# papilio_cam_board.net
KiCad netlist of a schematic drawn in EAGLE
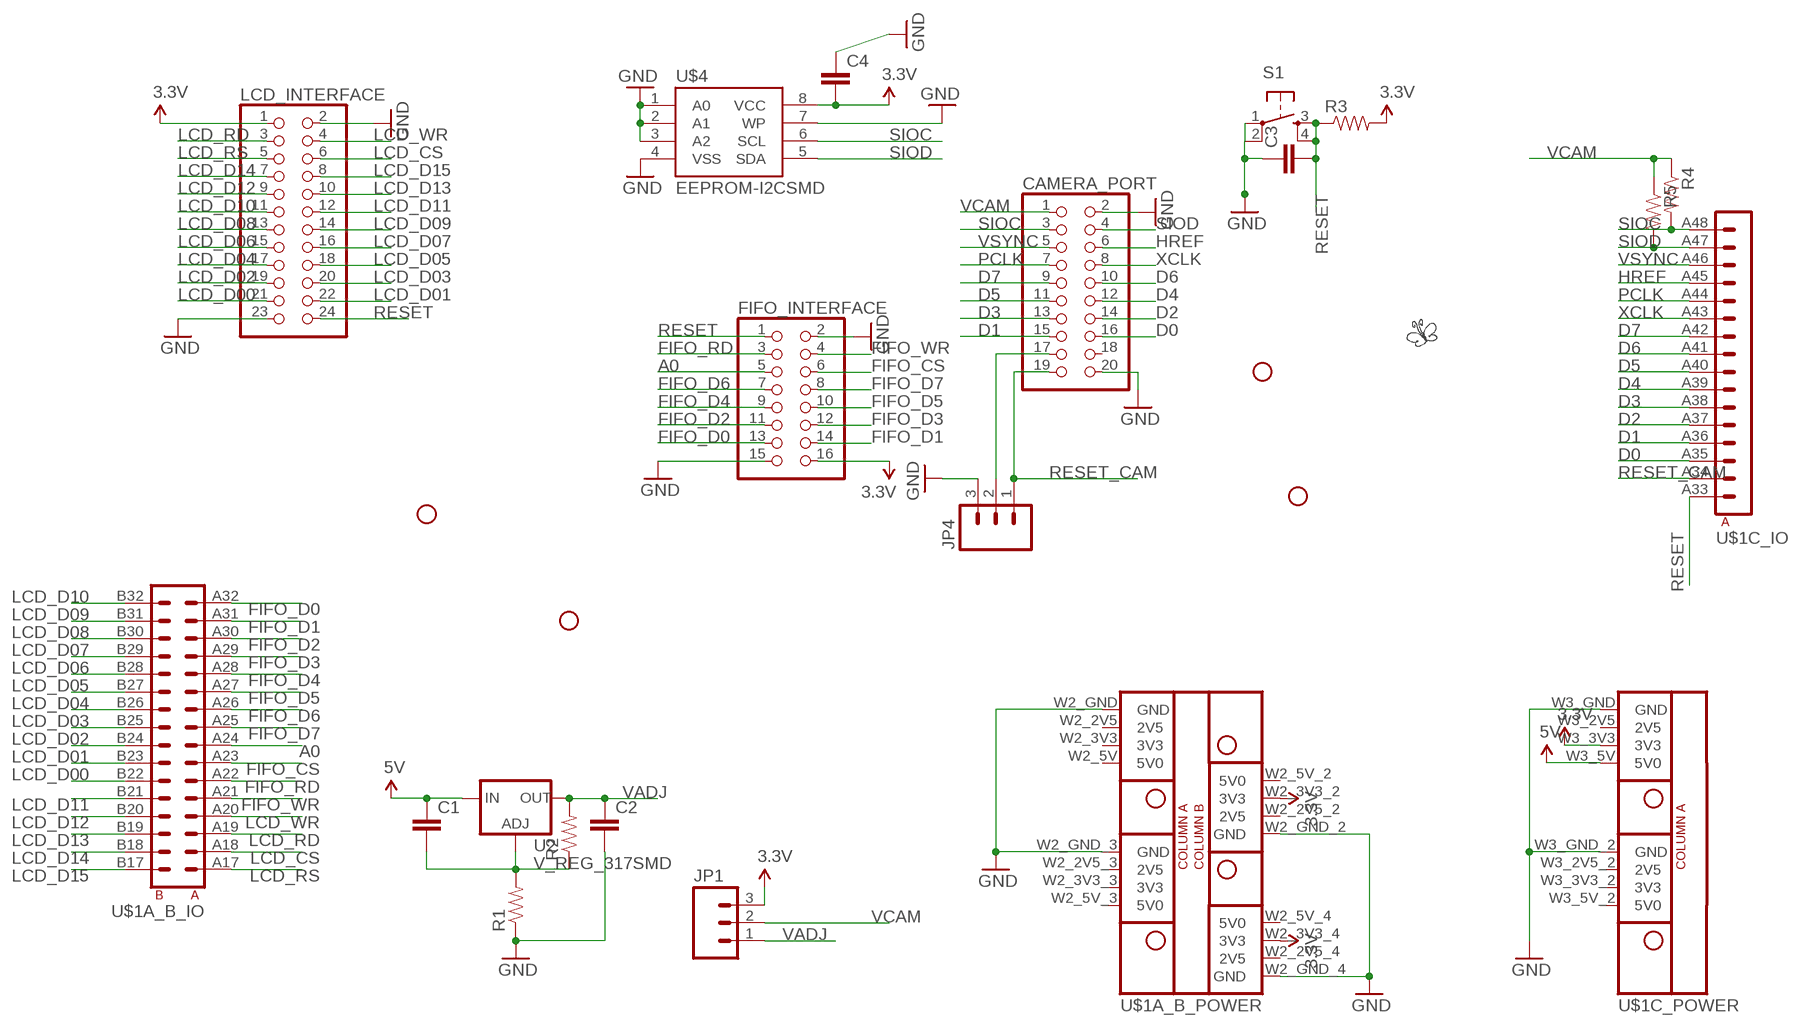
[diagram p0: schematic, sheet 1]

(export (version "E")
  (design (tool "Eeschema 10.0.6"))
  (components
    (comp (ref "C1")
      (value "CAP0805")
      (footprint "eagle-import:0805")
      (libsource (lib "eagle-import") (part "CAP0805"))
    )
    (comp (ref "C2")
      (value "CAP0805")
      (footprint "eagle-import:0805")
      (libsource (lib "eagle-import") (part "CAP0805"))
    )
    (comp (ref "C3")
      (value "CAP0805")
      (footprint "eagle-import:0805")
      (libsource (lib "eagle-import") (part "CAP0805"))
    )
    (comp (ref "C4")
      (value "CAP0805")
      (footprint "eagle-import:0805")
      (libsource (lib "eagle-import") (part "CAP0805"))
    )
    (comp (ref "CAMERA_PORT")
      (value "PINHD-2X10")
      (footprint "eagle-import:2X10")
      (libsource (lib "eagle-import") (part "PINHD-2X10"))
    )
    (comp (ref "FIFO_INTERFACE")
      (value "PINHD-2X8")
      (footprint "eagle-import:2X08")
      (libsource (lib "eagle-import") (part "PINHD-2X8"))
    )
    (comp (ref "JP1")
      (value "M03PTH")
      (footprint "eagle-import:1X03")
      (libsource (lib "eagle-import") (part "M03PTH"))
    )
    (comp (ref "JP2")
      (value "STAND-OFF")
      (footprint "eagle-import:STAND-OFF")
      (libsource (lib "eagle-import") (part "STAND-OFF"))
    )
    (comp (ref "JP3")
      (value "STAND-OFF")
      (footprint "eagle-import:STAND-OFF")
      (libsource (lib "eagle-import") (part "STAND-OFF"))
    )
    (comp (ref "JP4")
      (value "M03PTH")
      (footprint "eagle-import:1X03")
      (libsource (lib "eagle-import") (part "M03PTH"))
    )
    (comp (ref "JP5")
      (value "STAND-OFF")
      (footprint "eagle-import:STAND-OFF")
      (libsource (lib "eagle-import") (part "STAND-OFF"))
    )
    (comp (ref "JP7")
      (value "STAND-OFF")
      (footprint "eagle-import:STAND-OFF")
      (libsource (lib "eagle-import") (part "STAND-OFF"))
    )
    (comp (ref "LCD_INTERFACE")
      (value "PINHD-2X12")
      (footprint "eagle-import:2X12")
      (libsource (lib "eagle-import") (part "PINHD-2X12"))
    )
    (comp (ref "LOGO1")
      (value "BUTTERFLY_LOGO")
      (footprint "eagle-import:BUTTERFLY_LOGO")
      (libsource (lib "eagle-import") (part "BUTTERFLY_LOGO"))
    )
    (comp (ref "R1")
      (value "RESISTOR0805-RES")
      (footprint "eagle-import:0805")
      (libsource (lib "eagle-import") (part "RESISTOR0805-RES"))
    )
    (comp (ref "R2")
      (value "RESISTOR0805-RES")
      (footprint "eagle-import:0805")
      (libsource (lib "eagle-import") (part "RESISTOR0805-RES"))
    )
    (comp (ref "R3")
      (value "RESISTOR0805-RES")
      (footprint "eagle-import:0805")
      (libsource (lib "eagle-import") (part "RESISTOR0805-RES"))
    )
    (comp (ref "R4")
      (value "RESISTOR0805-RES")
      (footprint "eagle-import:0805")
      (libsource (lib "eagle-import") (part "RESISTOR0805-RES"))
    )
    (comp (ref "R5")
      (value "RESISTOR0805-RES")
      (footprint "eagle-import:0805")
      (libsource (lib "eagle-import") (part "RESISTOR0805-RES"))
    )
    (comp (ref "S1")
      (value "TAC_SWITCHSMD")
      (footprint "eagle-import:TACTILE_SWITCH_SMD")
      (libsource (lib "eagle-import") (part "TAC_SWITCHSMD"))
    )
    (comp (ref "U$1")
      (value "MEGAWING_FULL_P1MEGAWING_P1")
      (footprint "eagle-import:MEGAWING_FULL_NOHOLES_P1")
      (libsource (lib "eagle-import") (part "MEGAWING_FULL_P1MEGAWING_P1"))
    )
    (comp (ref "U$4")
      (value "EEPROM-I2CSMD")
      (footprint "eagle-import:SO08")
      (libsource (lib "eagle-import") (part "EEPROM-I2CSMD"))
    )
    (comp (ref "U2")
      (value "V_REG_317SMD")
      (footprint "eagle-import:SOT223")
      (libsource (lib "eagle-import") (part "V_REG_317SMD"))
    )
  )
  (nets
    (net (code "1") (name "/A0") (class "Default")
      (node (ref "FIFO_INTERFACE") (pin "5") (pinfunction "5_5") (pintype "passive"))
      (node (ref "U$1") (pin "A24") (pinfunction "A8_A24") (pintype "bidirectional"))
    )
    (net (code "2") (name "/D0") (class "Default")
      (node (ref "CAMERA_PORT") (pin "16") (pinfunction "16_16") (pintype "passive"))
      (node (ref "U$1") (pin "A35") (pinfunction "A3_A35") (pintype "bidirectional"))
    )
    (net (code "3") (name "/D1") (class "Default")
      (node (ref "CAMERA_PORT") (pin "15") (pinfunction "15_15") (pintype "passive"))
      (node (ref "U$1") (pin "A36") (pinfunction "A4_A36") (pintype "bidirectional"))
    )
    (net (code "4") (name "/D2") (class "Default")
      (node (ref "CAMERA_PORT") (pin "14") (pinfunction "14_14") (pintype "passive"))
      (node (ref "U$1") (pin "A37") (pinfunction "A5_A37") (pintype "bidirectional"))
    )
    (net (code "5") (name "/D3") (class "Default")
      (node (ref "CAMERA_PORT") (pin "13") (pinfunction "13_13") (pintype "passive"))
      (node (ref "U$1") (pin "A38") (pinfunction "A6_A38") (pintype "bidirectional"))
    )
    (net (code "6") (name "/D4") (class "Default")
      (node (ref "CAMERA_PORT") (pin "12") (pinfunction "12_12") (pintype "passive"))
      (node (ref "U$1") (pin "A39") (pinfunction "A7_A39") (pintype "bidirectional"))
    )
    (net (code "7") (name "/D5") (class "Default")
      (node (ref "CAMERA_PORT") (pin "11") (pinfunction "11_11") (pintype "passive"))
      (node (ref "U$1") (pin "A40") (pinfunction "A8_A40") (pintype "bidirectional"))
    )
    (net (code "8") (name "/D6") (class "Default")
      (node (ref "CAMERA_PORT") (pin "10") (pinfunction "10_10") (pintype "passive"))
      (node (ref "U$1") (pin "A41") (pinfunction "A9_A41") (pintype "bidirectional"))
    )
    (net (code "9") (name "/D7") (class "Default")
      (node (ref "CAMERA_PORT") (pin "9") (pinfunction "9_9") (pintype "passive"))
      (node (ref "U$1") (pin "A42") (pinfunction "A10_A42") (pintype "bidirectional"))
    )
    (net (code "10") (name "/FIFO_CS") (class "Default")
      (node (ref "FIFO_INTERFACE") (pin "6") (pinfunction "6_6") (pintype "passive"))
      (node (ref "U$1") (pin "A23") (pinfunction "A7_A23") (pintype "bidirectional"))
    )
    (net (code "11") (name "/FIFO_D0") (class "Default")
      (node (ref "FIFO_INTERFACE") (pin "13") (pinfunction "13_13") (pintype "passive"))
      (node (ref "U$1") (pin "A32") (pinfunction "A16_A32") (pintype "bidirectional"))
    )
    (net (code "12") (name "/FIFO_D1") (class "Default")
      (node (ref "FIFO_INTERFACE") (pin "14") (pinfunction "14_14") (pintype "passive"))
      (node (ref "U$1") (pin "A31") (pinfunction "A15_A31") (pintype "bidirectional"))
    )
    (net (code "13") (name "/FIFO_D2") (class "Default")
      (node (ref "FIFO_INTERFACE") (pin "11") (pinfunction "11_11") (pintype "passive"))
      (node (ref "U$1") (pin "A30") (pinfunction "A14_A30") (pintype "bidirectional"))
    )
    (net (code "14") (name "/FIFO_D3") (class "Default")
      (node (ref "FIFO_INTERFACE") (pin "12") (pinfunction "12_12") (pintype "passive"))
      (node (ref "U$1") (pin "A29") (pinfunction "A13_A29") (pintype "bidirectional"))
    )
    (net (code "15") (name "/FIFO_D4") (class "Default")
      (node (ref "FIFO_INTERFACE") (pin "9") (pinfunction "9_9") (pintype "passive"))
      (node (ref "U$1") (pin "A28") (pinfunction "A12_A28") (pintype "bidirectional"))
    )
    (net (code "16") (name "/FIFO_D5") (class "Default")
      (node (ref "FIFO_INTERFACE") (pin "10") (pinfunction "10_10") (pintype "passive"))
      (node (ref "U$1") (pin "A27") (pinfunction "A11_A27") (pintype "bidirectional"))
    )
    (net (code "17") (name "/FIFO_D6") (class "Default")
      (node (ref "FIFO_INTERFACE") (pin "7") (pinfunction "7_7") (pintype "passive"))
      (node (ref "U$1") (pin "A26") (pinfunction "A10_A26") (pintype "bidirectional"))
    )
    (net (code "18") (name "/FIFO_D7") (class "Default")
      (node (ref "FIFO_INTERFACE") (pin "8") (pinfunction "8_8") (pintype "passive"))
      (node (ref "U$1") (pin "A25") (pinfunction "A9_A25") (pintype "bidirectional"))
    )
    (net (code "19") (name "/FIFO_RD") (class "Default")
      (node (ref "FIFO_INTERFACE") (pin "3") (pinfunction "3_3") (pintype "passive"))
      (node (ref "U$1") (pin "A22") (pinfunction "A6_A22") (pintype "bidirectional"))
    )
    (net (code "20") (name "/FIFO_WR") (class "Default")
      (node (ref "FIFO_INTERFACE") (pin "4") (pinfunction "4_4") (pintype "passive"))
      (node (ref "U$1") (pin "A21") (pinfunction "A5_A21") (pintype "bidirectional"))
    )
    (net (code "21") (name "/HREF") (class "Default")
      (node (ref "CAMERA_PORT") (pin "6") (pinfunction "6_6") (pintype "passive"))
      (node (ref "U$1") (pin "A45") (pinfunction "A13_A45") (pintype "bidirectional"))
    )
    (net (code "22") (name "/LCD_CS") (class "Default")
      (node (ref "LCD_INTERFACE") (pin "6") (pinfunction "6_6") (pintype "passive"))
      (node (ref "U$1") (pin "A18") (pinfunction "A2_A18") (pintype "bidirectional"))
    )
    (net (code "23") (name "/LCD_D00") (class "Default")
      (node (ref "LCD_INTERFACE") (pin "21") (pinfunction "21_21") (pintype "passive"))
      (node (ref "U$1") (pin "B22") (pinfunction "B6_B22") (pintype "bidirectional"))
    )
    (net (code "24") (name "/LCD_D01") (class "Default")
      (node (ref "LCD_INTERFACE") (pin "22") (pinfunction "22_22") (pintype "passive"))
      (node (ref "U$1") (pin "B23") (pinfunction "B7_B23") (pintype "bidirectional"))
    )
    (net (code "25") (name "/LCD_D02") (class "Default")
      (node (ref "LCD_INTERFACE") (pin "19") (pinfunction "19_19") (pintype "passive"))
      (node (ref "U$1") (pin "B24") (pinfunction "B8_B24") (pintype "bidirectional"))
    )
    (net (code "26") (name "/LCD_D03") (class "Default")
      (node (ref "LCD_INTERFACE") (pin "20") (pinfunction "20_20") (pintype "passive"))
      (node (ref "U$1") (pin "B25") (pinfunction "B9_B25") (pintype "bidirectional"))
    )
    (net (code "27") (name "/LCD_D04") (class "Default")
      (node (ref "LCD_INTERFACE") (pin "17") (pinfunction "17_17") (pintype "passive"))
      (node (ref "U$1") (pin "B26") (pinfunction "B10_B26") (pintype "bidirectional"))
    )
    (net (code "28") (name "/LCD_D05") (class "Default")
      (node (ref "LCD_INTERFACE") (pin "18") (pinfunction "18_18") (pintype "passive"))
      (node (ref "U$1") (pin "B27") (pinfunction "B11_B27") (pintype "bidirectional"))
    )
    (net (code "29") (name "/LCD_D06") (class "Default")
      (node (ref "LCD_INTERFACE") (pin "15") (pinfunction "15_15") (pintype "passive"))
      (node (ref "U$1") (pin "B28") (pinfunction "B12_B28") (pintype "bidirectional"))
    )
    (net (code "30") (name "/LCD_D07") (class "Default")
      (node (ref "LCD_INTERFACE") (pin "16") (pinfunction "16_16") (pintype "passive"))
      (node (ref "U$1") (pin "B29") (pinfunction "B13_B29") (pintype "bidirectional"))
    )
    (net (code "31") (name "/LCD_D08") (class "Default")
      (node (ref "LCD_INTERFACE") (pin "13") (pinfunction "13_13") (pintype "passive"))
      (node (ref "U$1") (pin "B30") (pinfunction "B14_B30") (pintype "bidirectional"))
    )
    (net (code "32") (name "/LCD_D09") (class "Default")
      (node (ref "LCD_INTERFACE") (pin "14") (pinfunction "14_14") (pintype "passive"))
      (node (ref "U$1") (pin "B31") (pinfunction "B15_B31") (pintype "bidirectional"))
    )
    (net (code "33") (name "/LCD_D10") (class "Default")
      (node (ref "LCD_INTERFACE") (pin "11") (pinfunction "11_11") (pintype "passive"))
      (node (ref "U$1") (pin "B32") (pinfunction "B16_B32") (pintype "bidirectional"))
    )
    (net (code "34") (name "/LCD_D11") (class "Default")
      (node (ref "LCD_INTERFACE") (pin "12") (pinfunction "12_12") (pintype "passive"))
      (node (ref "U$1") (pin "B21") (pinfunction "B5_B21") (pintype "bidirectional"))
    )
    (net (code "35") (name "/LCD_D12") (class "Default")
      (node (ref "LCD_INTERFACE") (pin "9") (pinfunction "9_9") (pintype "passive"))
      (node (ref "U$1") (pin "B20") (pinfunction "B4_B20") (pintype "bidirectional"))
    )
    (net (code "36") (name "/LCD_D13") (class "Default")
      (node (ref "LCD_INTERFACE") (pin "10") (pinfunction "10_10") (pintype "passive"))
      (node (ref "U$1") (pin "B19") (pinfunction "B3_B19") (pintype "bidirectional"))
    )
    (net (code "37") (name "/LCD_D14") (class "Default")
      (node (ref "LCD_INTERFACE") (pin "7") (pinfunction "7_7") (pintype "passive"))
      (node (ref "U$1") (pin "B18") (pinfunction "B2_B18") (pintype "bidirectional"))
    )
    (net (code "38") (name "/LCD_D15") (class "Default")
      (node (ref "LCD_INTERFACE") (pin "8") (pinfunction "8_8") (pintype "passive"))
      (node (ref "U$1") (pin "B17") (pinfunction "B1_B17") (pintype "bidirectional"))
    )
    (net (code "39") (name "/LCD_RD") (class "Default")
      (node (ref "LCD_INTERFACE") (pin "3") (pinfunction "3_3") (pintype "passive"))
      (node (ref "U$1") (pin "A19") (pinfunction "A3_A19") (pintype "bidirectional"))
    )
    (net (code "40") (name "/LCD_RS") (class "Default")
      (node (ref "LCD_INTERFACE") (pin "5") (pinfunction "5_5") (pintype "passive"))
      (node (ref "U$1") (pin "A17") (pinfunction "A1_A17") (pintype "bidirectional"))
    )
    (net (code "41") (name "/LCD_WR") (class "Default")
      (node (ref "LCD_INTERFACE") (pin "4") (pinfunction "4_4") (pintype "passive"))
      (node (ref "U$1") (pin "A20") (pinfunction "A4_A20") (pintype "bidirectional"))
    )
    (net (code "42") (name "/PCLK") (class "Default")
      (node (ref "CAMERA_PORT") (pin "7") (pinfunction "7_7") (pintype "passive"))
      (node (ref "U$1") (pin "A44") (pinfunction "A12_A44") (pintype "bidirectional"))
    )
    (net (code "43") (name "/RESET") (class "Default")
      (node (ref "C3") (pin "2") (pinfunction "2_2") (pintype "passive"))
      (node (ref "FIFO_INTERFACE") (pin "1") (pinfunction "1_1") (pintype "passive"))
      (node (ref "LCD_INTERFACE") (pin "24") (pinfunction "24_24") (pintype "passive"))
      (node (ref "R3") (pin "1") (pinfunction "1_1") (pintype "passive"))
      (node (ref "S1") (pin "3") (pinfunction "3_3") (pintype "passive"))
      (node (ref "S1") (pin "4") (pinfunction "4_4") (pintype "passive"))
      (node (ref "U$1") (pin "A33") (pinfunction "A1_A33") (pintype "bidirectional"))
    )
    (net (code "44") (name "/RESET_CAM") (class "Default")
      (node (ref "CAMERA_PORT") (pin "19") (pinfunction "19_19") (pintype "passive"))
      (node (ref "JP4") (pin "1") (pinfunction "1_1") (pintype "passive"))
      (node (ref "U$1") (pin "A34") (pinfunction "A2_A34") (pintype "bidirectional"))
    )
    (net (code "45") (name "/SIOC") (class "Default")
      (node (ref "CAMERA_PORT") (pin "3") (pinfunction "3_3") (pintype "passive"))
      (node (ref "R4") (pin "2") (pinfunction "2_2") (pintype "passive"))
      (node (ref "U$1") (pin "A48") (pinfunction "A16_A48") (pintype "bidirectional"))
      (node (ref "U$4") (pin "6") (pinfunction "SCL_6") (pintype "bidirectional"))
    )
    (net (code "46") (name "/SIOD") (class "Default")
      (node (ref "CAMERA_PORT") (pin "4") (pinfunction "4_4") (pintype "passive"))
      (node (ref "R5") (pin "2") (pinfunction "2_2") (pintype "passive"))
      (node (ref "U$1") (pin "A47") (pinfunction "A15_A47") (pintype "bidirectional"))
      (node (ref "U$4") (pin "5") (pinfunction "SDA_5") (pintype "bidirectional"))
    )
    (net (code "47") (name "/VADJ") (class "Default")
      (node (ref "C2") (pin "1") (pinfunction "1_1") (pintype "passive"))
      (node (ref "JP1") (pin "1") (pinfunction "1_1") (pintype "passive"))
      (node (ref "R2") (pin "2") (pinfunction "2_2") (pintype "passive"))
      (node (ref "U2") (pin "2") (pinfunction "OUT_2") (pintype "output"))
    )
    (net (code "48") (name "/VCAM") (class "Default")
      (node (ref "CAMERA_PORT") (pin "1") (pinfunction "1_1") (pintype "passive"))
      (node (ref "JP1") (pin "2") (pinfunction "2_2") (pintype "passive"))
      (node (ref "R4") (pin "1") (pinfunction "1_1") (pintype "passive"))
      (node (ref "R5") (pin "1") (pinfunction "1_1") (pintype "passive"))
    )
    (net (code "49") (name "/VSYNC") (class "Default")
      (node (ref "CAMERA_PORT") (pin "5") (pinfunction "5_5") (pintype "passive"))
      (node (ref "U$1") (pin "A46") (pinfunction "A14_A46") (pintype "bidirectional"))
    )
    (net (code "50") (name "/XCLK") (class "Default")
      (node (ref "CAMERA_PORT") (pin "8") (pinfunction "8_8") (pintype "passive"))
      (node (ref "U$1") (pin "A43") (pinfunction "A11_A43") (pintype "bidirectional"))
    )
    (net (code "51") (name "3.3V") (class "Default")
      (node (ref "C4") (pin "2") (pinfunction "2_2") (pintype "passive"))
      (node (ref "FIFO_INTERFACE") (pin "16") (pinfunction "16_16") (pintype "passive"))
      (node (ref "JP1") (pin "3") (pinfunction "3_3") (pintype "passive"))
      (node (ref "LCD_INTERFACE") (pin "1") (pinfunction "1_1") (pintype "passive"))
      (node (ref "R3") (pin "2") (pinfunction "2_2") (pintype "passive"))
      (node (ref "U$1") (pin "W2_3V3_2") (pinfunction "3V3_W2_3V3_2") (pintype "passive"))
      (node (ref "U$1") (pin "W2_3V3_4") (pinfunction "3V3_W2_3V3_4") (pintype "passive"))
      (node (ref "U$1") (pin "W3_3V3") (pinfunction "3V3_W3_3V3") (pintype "passive"))
      (node (ref "U$4") (pin "8") (pinfunction "VCC_8") (pintype "power_in"))
    )
    (net (code "52") (name "5V") (class "Default")
      (node (ref "C1") (pin "1") (pinfunction "1_1") (pintype "passive"))
      (node (ref "U$1") (pin "W3_5V") (pinfunction "5V0_W3_5V") (pintype "passive"))
      (node (ref "U2") (pin "3") (pinfunction "IN_3") (pintype "input"))
    )
    (net (code "53") (name "GND") (class "Default")
      (node (ref "C2") (pin "2") (pinfunction "2_2") (pintype "passive"))
      (node (ref "C3") (pin "1") (pinfunction "1_1") (pintype "passive"))
      (node (ref "C4") (pin "1") (pinfunction "1_1") (pintype "passive"))
      (node (ref "CAMERA_PORT") (pin "2") (pinfunction "2_2") (pintype "passive"))
      (node (ref "CAMERA_PORT") (pin "20") (pinfunction "20_20") (pintype "passive"))
      (node (ref "FIFO_INTERFACE") (pin "15") (pinfunction "15_15") (pintype "passive"))
      (node (ref "FIFO_INTERFACE") (pin "2") (pinfunction "2_2") (pintype "passive"))
      (node (ref "JP4") (pin "3") (pinfunction "3_3") (pintype "passive"))
      (node (ref "LCD_INTERFACE") (pin "2") (pinfunction "2_2") (pintype "passive"))
      (node (ref "LCD_INTERFACE") (pin "23") (pinfunction "23_23") (pintype "passive"))
      (node (ref "R1") (pin "1") (pinfunction "1_1") (pintype "passive"))
      (node (ref "S1") (pin "1") (pinfunction "1_1") (pintype "passive"))
      (node (ref "S1") (pin "2") (pinfunction "2_2") (pintype "passive"))
      (node (ref "U$1") (pin "W2_GND") (pinfunction "GND_W2_GND") (pintype "power_in"))
      (node (ref "U$1") (pin "W2_GND_2") (pinfunction "GND_W2_GND_2") (pintype "power_in"))
      (node (ref "U$1") (pin "W2_GND_3") (pinfunction "GND_W2_GND_3") (pintype "power_in"))
      (node (ref "U$1") (pin "W2_GND_4") (pinfunction "GND_W2_GND_4") (pintype "power_in"))
      (node (ref "U$1") (pin "W3_GND") (pinfunction "GND_W3_GND") (pintype "power_in"))
      (node (ref "U$1") (pin "W3_GND_2") (pinfunction "GND_W3_GND_2") (pintype "power_in"))
      (node (ref "U$4") (pin "1") (pinfunction "A0_1") (pintype "bidirectional"))
      (node (ref "U$4") (pin "2") (pinfunction "A1_2") (pintype "bidirectional"))
      (node (ref "U$4") (pin "3") (pinfunction "A2_3") (pintype "bidirectional"))
      (node (ref "U$4") (pin "4") (pinfunction "VSS_4") (pintype "power_in"))
      (node (ref "U$4") (pin "7") (pinfunction "WP_7") (pintype "bidirectional"))
    )
    (net (code "54") (name "Net-(CAMERA_PORT-Pad17)") (class "Default")
      (node (ref "CAMERA_PORT") (pin "17") (pinfunction "17_17") (pintype "passive"))
      (node (ref "JP4") (pin "2") (pinfunction "2_2") (pintype "passive"))
    )
    (net (code "55") (name "Net-(U2-ADJ)") (class "Default")
      (node (ref "C1") (pin "2") (pinfunction "2_2") (pintype "passive"))
      (node (ref "R1") (pin "2") (pinfunction "2_2") (pintype "passive"))
      (node (ref "R2") (pin "1") (pinfunction "1_1") (pintype "passive"))
      (node (ref "U2") (pin "1") (pinfunction "ADJ_1") (pintype "input"))
    )
    (net (code "56") (name "unconnected-(CAMERA_PORT-Pad18)") (class "Default")
      (node (ref "CAMERA_PORT") (pin "18") (pinfunction "18_18") (pintype "passive"))
    )
    (net (code "57") (name "unconnected-(U$1B-2V5-PadW2_2V5)") (class "Default")
      (node (ref "U$1") (pin "W2_2V5") (pinfunction "2V5_W2_2V5") (pintype "passive"))
    )
    (net (code "58") (name "unconnected-(U$1B-2V5-PadW2_2V5_2)") (class "Default")
      (node (ref "U$1") (pin "W2_2V5_2") (pinfunction "2V5_W2_2V5_2") (pintype "passive"))
    )
    (net (code "59") (name "unconnected-(U$1B-2V5-PadW2_2V5_3)") (class "Default")
      (node (ref "U$1") (pin "W2_2V5_3") (pinfunction "2V5_W2_2V5_3") (pintype "passive"))
    )
    (net (code "60") (name "unconnected-(U$1B-2V5-PadW2_2V5_4)") (class "Default")
      (node (ref "U$1") (pin "W2_2V5_4") (pinfunction "2V5_W2_2V5_4") (pintype "passive"))
    )
    (net (code "61") (name "unconnected-(U$1B-3V3-PadW2_3V3)") (class "Default")
      (node (ref "U$1") (pin "W2_3V3") (pinfunction "3V3_W2_3V3") (pintype "passive"))
    )
    (net (code "62") (name "unconnected-(U$1B-3V3-PadW2_3V3_3)") (class "Default")
      (node (ref "U$1") (pin "W2_3V3_3") (pinfunction "3V3_W2_3V3_3") (pintype "passive"))
    )
    (net (code "63") (name "unconnected-(U$1B-5V0-PadW2_5V)") (class "Default")
      (node (ref "U$1") (pin "W2_5V") (pinfunction "5V0_W2_5V") (pintype "passive"))
    )
    (net (code "64") (name "unconnected-(U$1B-5V0-PadW2_5V_2)") (class "Default")
      (node (ref "U$1") (pin "W2_5V_2") (pinfunction "5V0_W2_5V_2") (pintype "passive"))
    )
    (net (code "65") (name "unconnected-(U$1B-5V0-PadW2_5V_3)") (class "Default")
      (node (ref "U$1") (pin "W2_5V_3") (pinfunction "5V0_W2_5V_3") (pintype "passive"))
    )
    (net (code "66") (name "unconnected-(U$1B-5V0-PadW2_5V_4)") (class "Default")
      (node (ref "U$1") (pin "W2_5V_4") (pinfunction "5V0_W2_5V_4") (pintype "passive"))
    )
    (net (code "67") (name "unconnected-(U$1D-2V5-PadW3_2V5)") (class "Default")
      (node (ref "U$1") (pin "W3_2V5") (pinfunction "2V5_W3_2V5") (pintype "passive"))
    )
    (net (code "68") (name "unconnected-(U$1D-2V5-PadW3_2V5_2)") (class "Default")
      (node (ref "U$1") (pin "W3_2V5_2") (pinfunction "2V5_W3_2V5_2") (pintype "passive"))
    )
    (net (code "69") (name "unconnected-(U$1D-3V3-PadW3_3V3_2)") (class "Default")
      (node (ref "U$1") (pin "W3_3V3_2") (pinfunction "3V3_W3_3V3_2") (pintype "passive"))
    )
    (net (code "70") (name "unconnected-(U$1D-5V0-PadW3_5V_2)") (class "Default")
      (node (ref "U$1") (pin "W3_5V_2") (pinfunction "5V0_W3_5V_2") (pintype "passive"))
    )
  )
)
